# ultra-violet-tooth-sensor-mk-3_2.net
KiCad netlist of a schematic drawn in EAGLE
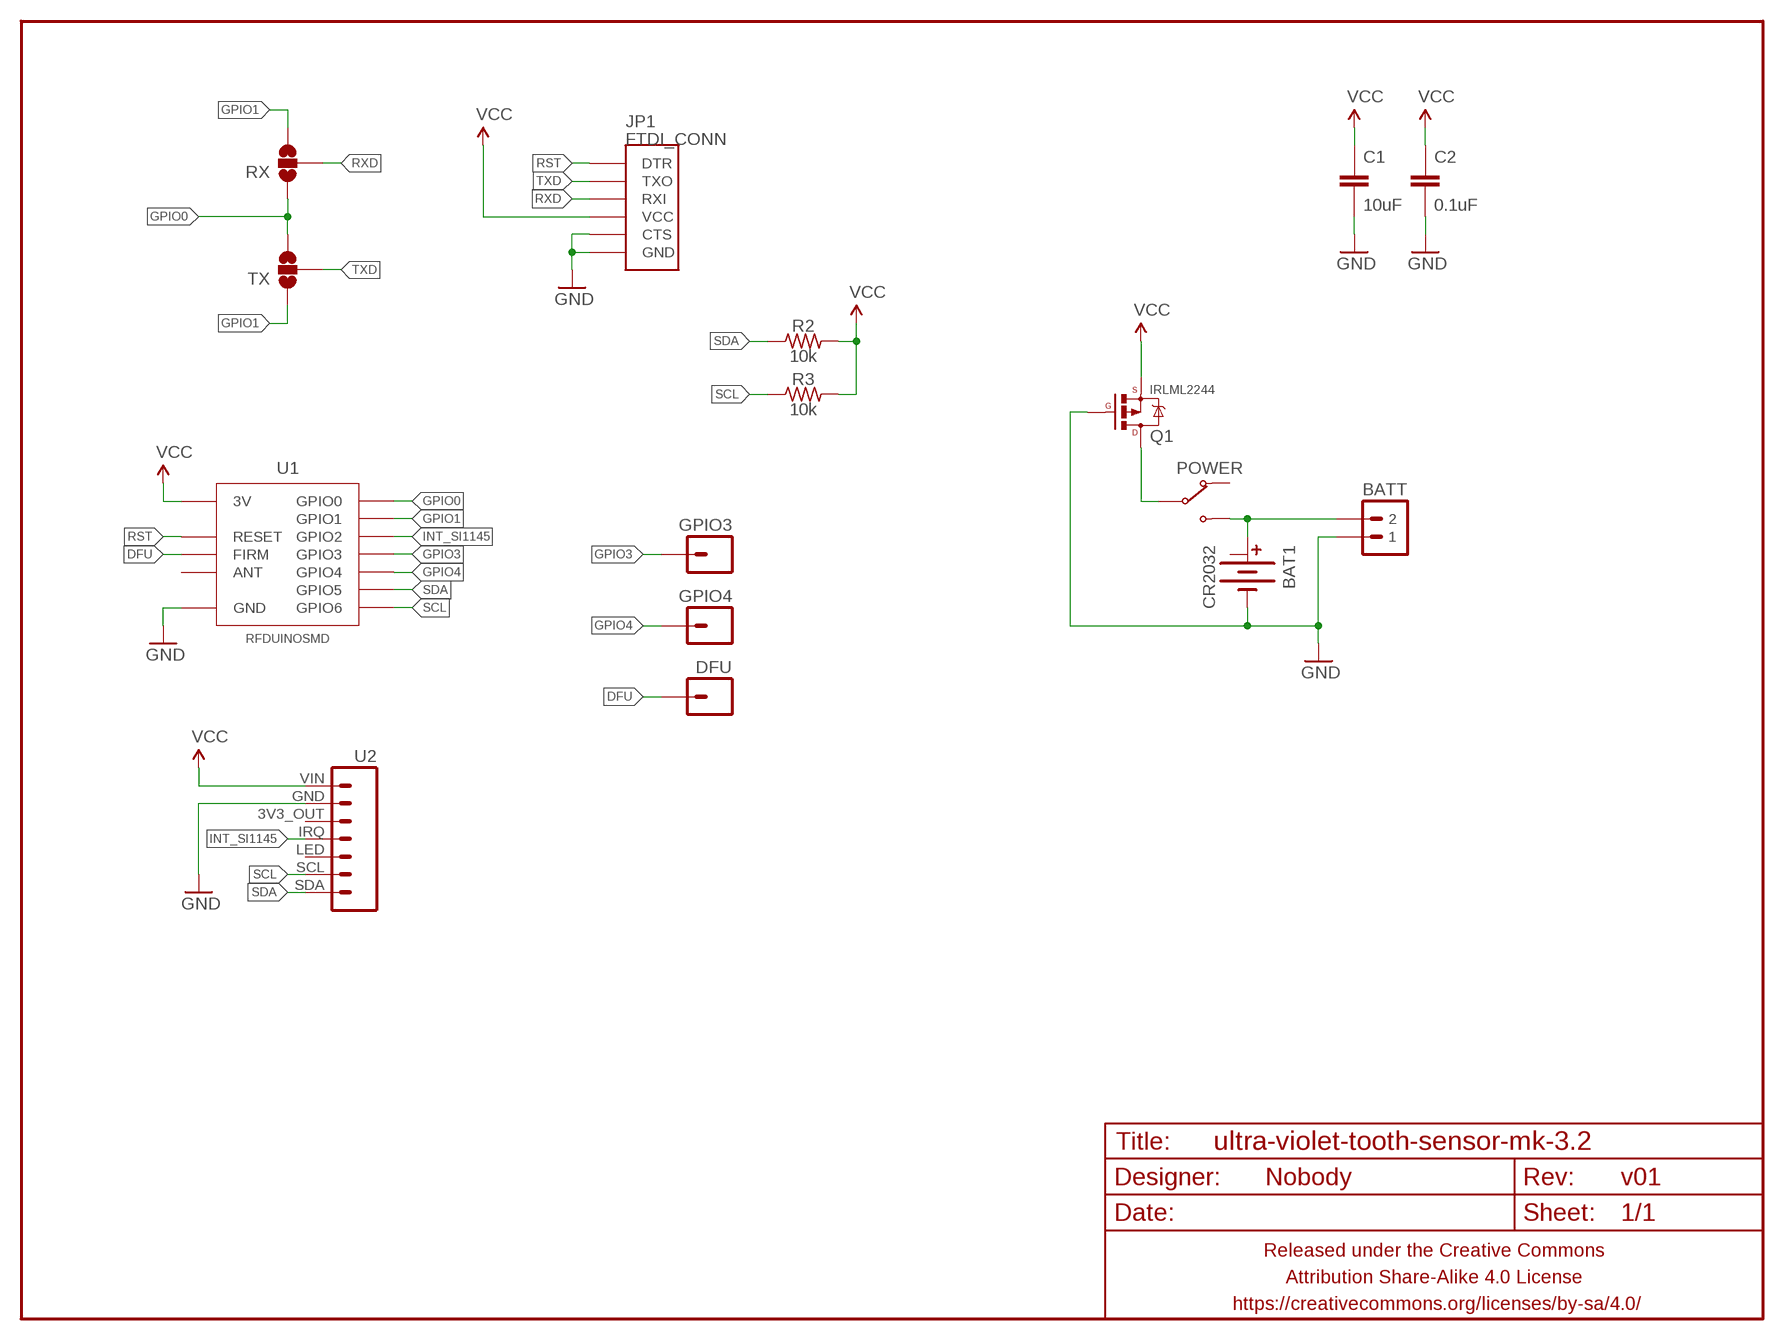
[diagram p0: schematic, sheet 1]

(export (version "E")
  (design (tool "Eeschema 10.0.6"))
  (components
    (comp (ref "BAT1")
      (value "CR2032")
      (footprint "eagle-import:BATTCON_20MM_MINE_STAHPIT")
      (libsource (lib "eagle-import") (part "BATTERY-COINCR2032_SMD_TIGHT"))
    )
    (comp (ref "BATT")
      (value "M02PTH-CENTERED-R+")
      (footprint "eagle-import:1X02-CENTER-R+")
      (libsource (lib "eagle-import") (part "M02PTH-CENTERED-R+"))
    )
    (comp (ref "C1")
      (value "10uF")
      (footprint "eagle-import:C1206")
      (libsource (lib "eagle-import") (part "CAPACITOR-CERAMICC1206"))
    )
    (comp (ref "C2")
      (value "0.1uF")
      (footprint "eagle-import:C0805")
      (libsource (lib "eagle-import") (part "CAPACITOR-CERAMICC0805"))
    )
    (comp (ref "DFU")
      (value "M01SMD_1.5X2MM")
      (footprint "eagle-import:1X01_1.5X2MM")
      (libsource (lib "eagle-import") (part "M01SMD_1.5X2MM"))
    )
    (comp (ref "FRAME1")
      (value "FRAME-LETTERNO_PACKAGE")
      (footprint "eagle-import:DUMMY")
      (fields (field (name "DESIGNER") "Nobody"))
      (libsource (lib "eagle-import") (part "FRAME-LETTERNO_PACKAGE"))
    )
    (comp (ref "GPIO3")
      (value "M01SMD_1.5X2MM")
      (footprint "eagle-import:1X01_1.5X2MM")
      (libsource (lib "eagle-import") (part "M01SMD_1.5X2MM"))
    )
    (comp (ref "GPIO4")
      (value "M01SMD_1.5X2MM")
      (footprint "eagle-import:1X01_1.5X2MM")
      (libsource (lib "eagle-import") (part "M01SMD_1.5X2MM"))
    )
    (comp (ref "JP1")
      (value "FTDI_CONN")
      (footprint "eagle-import:FTDI_CONN")
      (libsource (lib "eagle-import") (part "FTDI_CONN"))
    )
    (comp (ref "POWER")
      (value "SWITCH-SPDTPTH-RA-2.54MM")
      (footprint "eagle-import:SPDT-RA-2.54MM")
      (libsource (lib "eagle-import") (part "SWITCH-SPDTPTH-RA-2.54MM"))
    )
    (comp (ref "Q1")
      (value "IRLML2244")
      (footprint "eagle-import:SOT23-3")
      (libsource (lib "eagle-import") (part "MOSFET-PCHANNELIRLML2244"))
    )
    (comp (ref "R2")
      (value "10k")
      (footprint "eagle-import:R0805")
      (libsource (lib "eagle-import") (part "RESISTORR0805"))
    )
    (comp (ref "R3")
      (value "10k")
      (footprint "eagle-import:R0805")
      (libsource (lib "eagle-import") (part "RESISTORR0805"))
    )
    (comp (ref "RX")
      (value "JUMPER-PAD-3-NOFULL_BOX_SILK")
      (footprint "eagle-import:PAD-JUMPER-3-NO_YES_SILK_FULL_BOX")
      (libsource (lib "eagle-import") (part "JUMPER-PAD-3-NOFULL_BOX_SILK"))
    )
    (comp (ref "TX")
      (value "JUMPER-PAD-3-NOFULL_BOX_SILK")
      (footprint "eagle-import:PAD-JUMPER-3-NO_YES_SILK_FULL_BOX")
      (libsource (lib "eagle-import") (part "JUMPER-PAD-3-NOFULL_BOX_SILK"))
    )
    (comp (ref "U1")
      (value "RFDUINOSMD")
      (footprint "eagle-import:RFDUINO-SMD")
      (libsource (lib "eagle-import") (part "RFDUINOSMD"))
    )
    (comp (ref "U2")
      (value "ADAFRUIT-SI1145-BREAKOUTNOHOLEY")
      (footprint "eagle-import:ADAFRUIT-SI1145-BREAKOUT-NOHOLES")
      (libsource (lib "eagle-import") (part "ADAFRUIT-SI1145-BREAKOUTNOHOLEY"))
    )
  )
  (nets
    (net (code "1") (name "DFU") (class "Default")
      (node (ref "DFU") (pin "P$1") (pinfunction "1_P$1") (pintype "passive"))
      (node (ref "U1") (pin "FACTORY") (pinfunction "FIRM_FACTORY") (pintype "bidirectional"))
    )
    (net (code "2") (name "GND") (class "Default")
      (node (ref "BAT1") (pin "BOTTOM") (pinfunction "-_BOTTOM") (pintype "bidirectional"))
      (node (ref "BATT") (pin "1") (pinfunction "1_1") (pintype "passive"))
      (node (ref "C1") (pin "2") (pinfunction "2_2") (pintype "passive"))
      (node (ref "C2") (pin "2") (pinfunction "2_2") (pintype "passive"))
      (node (ref "JP1") (pin "CTS") (pinfunction "CTS_CTS") (pintype "bidirectional"))
      (node (ref "JP1") (pin "GND") (pinfunction "GND_GND") (pintype "bidirectional"))
      (node (ref "Q1") (pin "1") (pinfunction "G_1") (pintype "passive"))
      (node (ref "U1") (pin "GND@1") (pinfunction "GND_GND@1") (pintype "bidirectional"))
      (node (ref "U1") (pin "GND@2") (pinfunction "GND_GND@2") (pintype "bidirectional"))
      (node (ref "U1") (pin "GND@3") (pinfunction "GND_GND@3") (pintype "bidirectional"))
      (node (ref "U1") (pin "GND@4") (pinfunction "GND_GND@4") (pintype "bidirectional"))
      (node (ref "U1") (pin "GND@5") (pinfunction "GND_GND@5") (pintype "bidirectional"))
      (node (ref "U1") (pin "GND@6") (pinfunction "GND_GND@6") (pintype "bidirectional"))
      (node (ref "U1") (pin "GND@7") (pinfunction "GND_GND@7") (pintype "bidirectional"))
      (node (ref "U1") (pin "GND@8") (pinfunction "GND_GND@8") (pintype "bidirectional"))
      (node (ref "U2") (pin "GND") (pinfunction "GND_GND") (pintype "passive"))
    )
    (net (code "3") (name "GPIO0") (class "Default")
      (node (ref "RX") (pin "1") (pinfunction "1_1") (pintype "passive"))
      (node (ref "TX") (pin "3") (pinfunction "3_3") (pintype "passive"))
      (node (ref "U1") (pin "GPIO0") (pinfunction "GPIO0_GPIO0") (pintype "bidirectional"))
    )
    (net (code "4") (name "GPIO1") (class "Default")
      (node (ref "RX") (pin "3") (pinfunction "3_3") (pintype "passive"))
      (node (ref "TX") (pin "1") (pinfunction "1_1") (pintype "passive"))
      (node (ref "U1") (pin "GPIO1") (pinfunction "GPIO1_GPIO1") (pintype "bidirectional"))
    )
    (net (code "5") (name "GPIO3") (class "Default")
      (node (ref "GPIO3") (pin "P$1") (pinfunction "1_P$1") (pintype "passive"))
      (node (ref "U1") (pin "GPIO3") (pinfunction "GPIO3_GPIO3") (pintype "bidirectional"))
    )
    (net (code "6") (name "GPIO4") (class "Default")
      (node (ref "GPIO4") (pin "P$1") (pinfunction "1_P$1") (pintype "passive"))
      (node (ref "U1") (pin "GPIO4") (pinfunction "GPIO4_GPIO4") (pintype "bidirectional"))
    )
    (net (code "7") (name "INT_SI1145") (class "Default")
      (node (ref "U1") (pin "GPIO2") (pinfunction "GPIO2_GPIO2") (pintype "bidirectional"))
      (node (ref "U2") (pin "IRQ") (pinfunction "IRQ_IRQ") (pintype "passive"))
    )
    (net (code "8") (name "Net-(BAT1-+)") (class "Default")
      (node (ref "BAT1") (pin "TOP@1") (pinfunction "+_TOP@1") (pintype "bidirectional"))
      (node (ref "BATT") (pin "2") (pinfunction "2_2") (pintype "passive"))
      (node (ref "POWER") (pin "3") (pinfunction "NO_3") (pintype "passive"))
    )
    (net (code "9") (name "Net-(POWER-COM)") (class "Default")
      (node (ref "POWER") (pin "2") (pinfunction "COM_2") (pintype "passive"))
      (node (ref "Q1") (pin "3") (pinfunction "D_3") (pintype "passive"))
    )
    (net (code "10") (name "RST") (class "Default")
      (node (ref "JP1") (pin "DTR") (pinfunction "DTR_DTR") (pintype "bidirectional"))
      (node (ref "U1") (pin "RESET") (pinfunction "RESET_RESET") (pintype "bidirectional"))
    )
    (net (code "11") (name "RXD") (class "Default")
      (node (ref "JP1") (pin "RXI") (pinfunction "RXI_RXI") (pintype "bidirectional"))
      (node (ref "RX") (pin "2") (pinfunction "2_2") (pintype "passive"))
    )
    (net (code "12") (name "SCL") (class "Default")
      (node (ref "R3") (pin "1") (pinfunction "1_1") (pintype "passive"))
      (node (ref "U1") (pin "GPIO6") (pinfunction "GPIO6_GPIO6") (pintype "bidirectional"))
      (node (ref "U2") (pin "SCL") (pinfunction "SCL_SCL") (pintype "passive"))
    )
    (net (code "13") (name "SDA") (class "Default")
      (node (ref "R2") (pin "1") (pinfunction "1_1") (pintype "passive"))
      (node (ref "U1") (pin "GPIO5") (pinfunction "GPIO5_GPIO5") (pintype "bidirectional"))
      (node (ref "U2") (pin "SDA") (pinfunction "SDA_SDA") (pintype "passive"))
    )
    (net (code "14") (name "TXD") (class "Default")
      (node (ref "JP1") (pin "TXO") (pinfunction "TXO_TXO") (pintype "bidirectional"))
      (node (ref "TX") (pin "2") (pinfunction "2_2") (pintype "passive"))
    )
    (net (code "15") (name "VCC") (class "Default")
      (node (ref "C1") (pin "1") (pinfunction "1_1") (pintype "passive"))
      (node (ref "C2") (pin "1") (pinfunction "1_1") (pintype "passive"))
      (node (ref "JP1") (pin "VCC") (pinfunction "VCC_VCC") (pintype "bidirectional"))
      (node (ref "Q1") (pin "2") (pinfunction "S_2") (pintype "passive"))
      (node (ref "R2") (pin "2") (pinfunction "2_2") (pintype "passive"))
      (node (ref "R3") (pin "2") (pinfunction "2_2") (pintype "passive"))
      (node (ref "U1") (pin "3V") (pinfunction "3V_3V") (pintype "bidirectional"))
      (node (ref "U2") (pin "VIN") (pinfunction "VIN_VIN") (pintype "passive"))
    )
    (net (code "16") (name "unconnected-(BAT1-+1-PadTOP@2)") (class "Default")
      (node (ref "BAT1") (pin "TOP@2") (pinfunction "+1_TOP@2") (pintype "bidirectional"))
    )
    (net (code "17") (name "unconnected-(POWER-NC-Pad1)") (class "Default")
      (node (ref "POWER") (pin "1") (pinfunction "NC_1") (pintype "passive"))
    )
    (net (code "18") (name "unconnected-(U1-PadANT)") (class "Default")
      (node (ref "U1") (pin "ANT") (pinfunction "ANT_ANT") (pintype "bidirectional"))
    )
    (net (code "19") (name "unconnected-(U2-Pad3V3_OUT)") (class "Default")
      (node (ref "U2") (pin "3V3_OUT") (pinfunction "3V3_OUT_3V3_OUT") (pintype "passive"))
    )
    (net (code "20") (name "unconnected-(U2-PadLED)") (class "Default")
      (node (ref "U2") (pin "LED") (pinfunction "LED_LED") (pintype "passive"))
    )
  )
)
